# optical_meter_reader.net
KiCad netlist of a schematic drawn in EAGLE
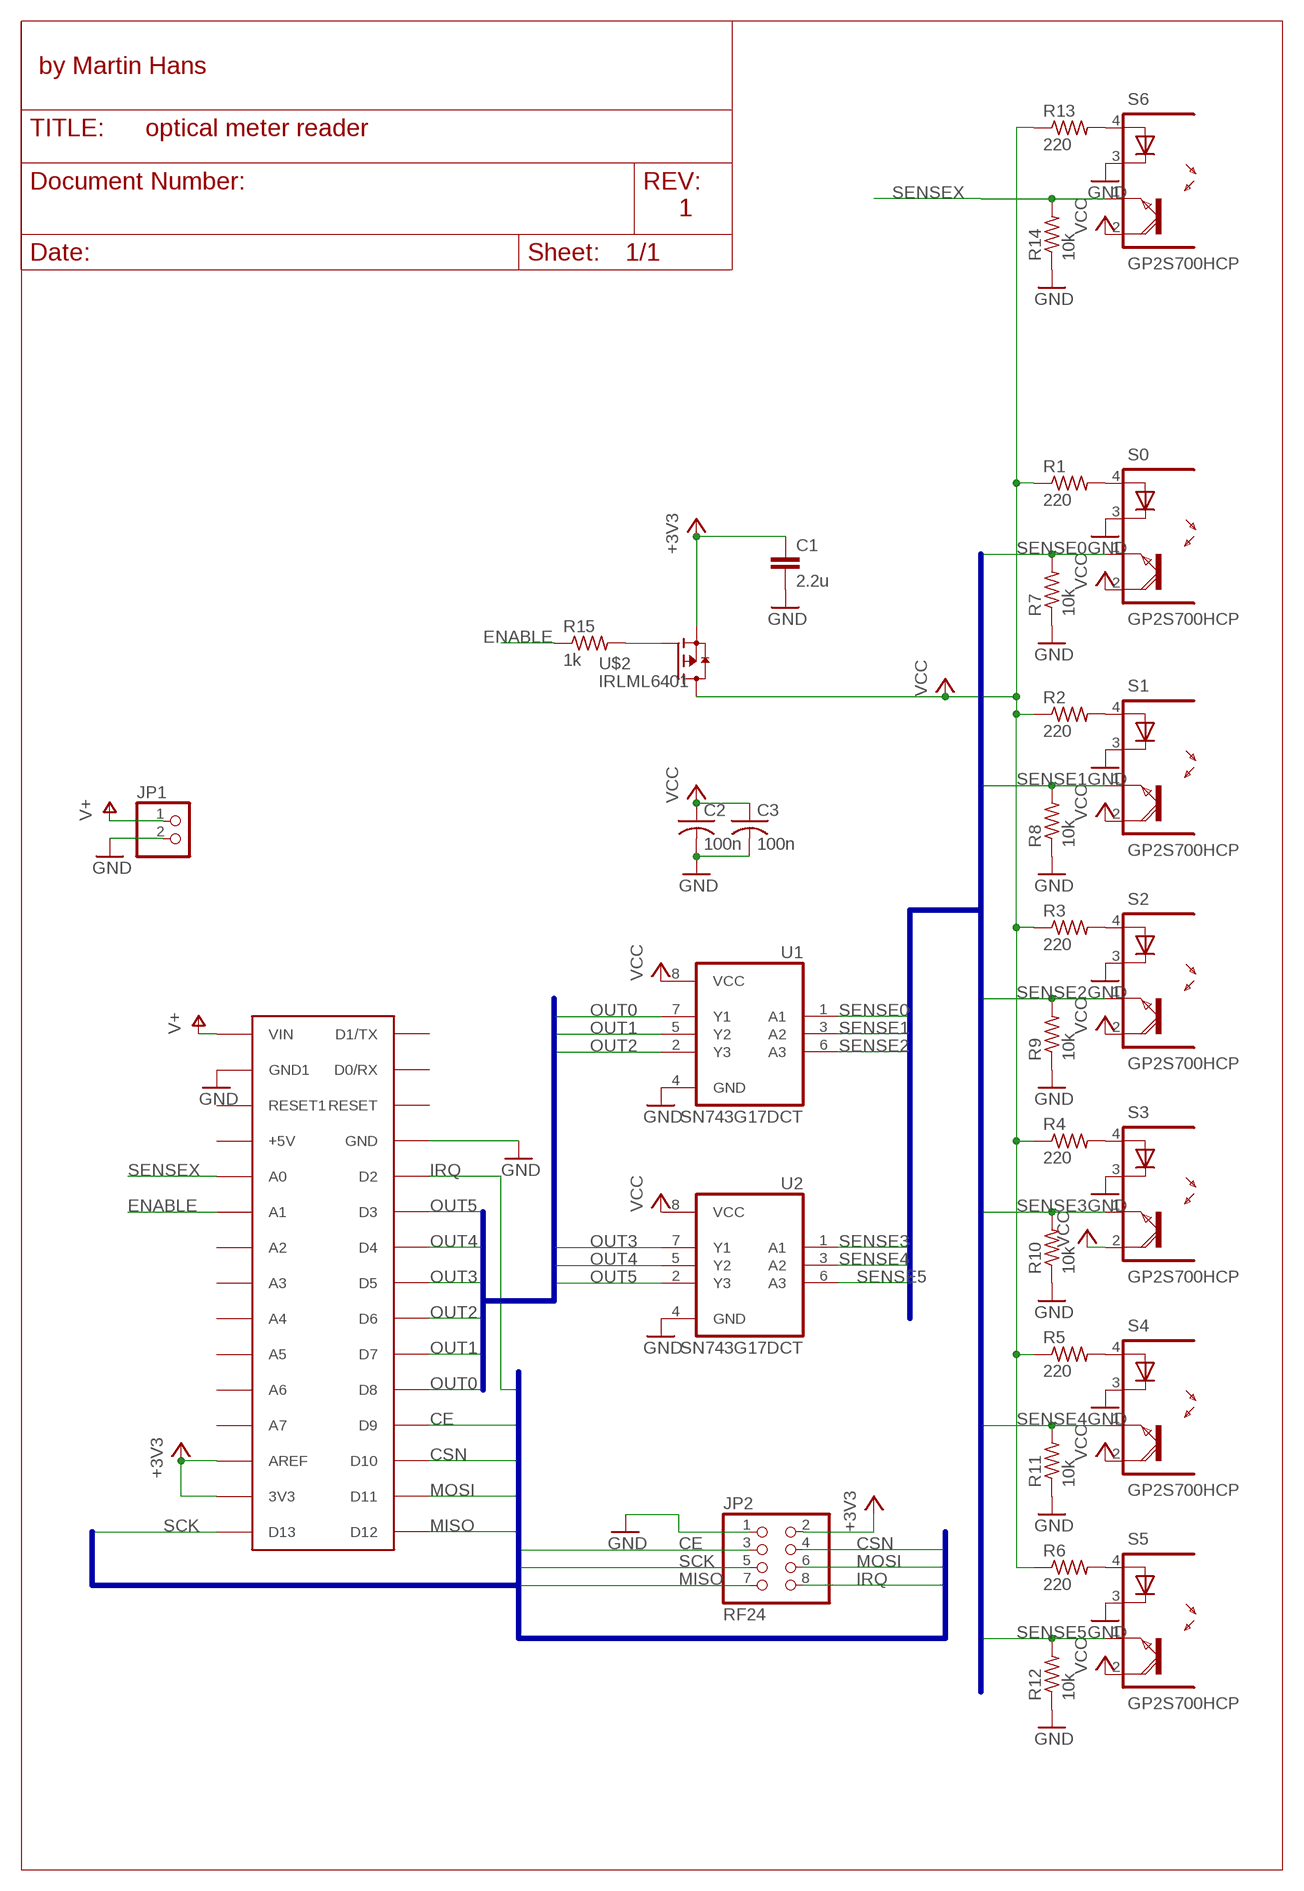
[diagram p0: schematic, sheet 1]

(export (version "E")
  (design (tool "Eeschema 10.0.6"))
  (components
    (comp (ref "C1")
      (value "2.2u")
      (footprint "eagle-import:C0603")
      (libsource (lib "eagle-import") (part "C-EUC0603"))
    )
    (comp (ref "C2")
      (value "100n")
      (footprint "eagle-import:C0603")
      (libsource (lib "eagle-import") (part "C-USC0603"))
    )
    (comp (ref "C3")
      (value "100n")
      (footprint "eagle-import:C0603")
      (libsource (lib "eagle-import") (part "C-USC0603"))
    )
    (comp (ref "JP1")
      (value "PINHD-1X2")
      (footprint "eagle-import:1X02")
      (libsource (lib "eagle-import") (part "PINHD-1X2"))
    )
    (comp (ref "JP2")
      (value "RF24")
      (footprint "eagle-import:2X04")
      (libsource (lib "eagle-import") (part "PINHD-2X4"))
    )
    (comp (ref "R1")
      (value "220")
      (footprint "eagle-import:R0603")
      (libsource (lib "eagle-import") (part "R-US_R0603"))
    )
    (comp (ref "R2")
      (value "220")
      (footprint "eagle-import:R0603")
      (libsource (lib "eagle-import") (part "R-US_R0603"))
    )
    (comp (ref "R3")
      (value "220")
      (footprint "eagle-import:R0603")
      (libsource (lib "eagle-import") (part "R-US_R0603"))
    )
    (comp (ref "R4")
      (value "220")
      (footprint "eagle-import:R0603")
      (libsource (lib "eagle-import") (part "R-US_R0603"))
    )
    (comp (ref "R5")
      (value "220")
      (footprint "eagle-import:R0603")
      (libsource (lib "eagle-import") (part "R-US_R0603"))
    )
    (comp (ref "R6")
      (value "220")
      (footprint "eagle-import:R0603")
      (libsource (lib "eagle-import") (part "R-US_R0603"))
    )
    (comp (ref "R7")
      (value "10k")
      (footprint "eagle-import:R0603")
      (libsource (lib "eagle-import") (part "R-US_R0603"))
    )
    (comp (ref "R8")
      (value "10k")
      (footprint "eagle-import:R0603")
      (libsource (lib "eagle-import") (part "R-US_R0603"))
    )
    (comp (ref "R9")
      (value "10k")
      (footprint "eagle-import:R0603")
      (libsource (lib "eagle-import") (part "R-US_R0603"))
    )
    (comp (ref "R10")
      (value "10k")
      (footprint "eagle-import:R0603")
      (libsource (lib "eagle-import") (part "R-US_R0603"))
    )
    (comp (ref "R11")
      (value "10k")
      (footprint "eagle-import:R0603")
      (libsource (lib "eagle-import") (part "R-US_R0603"))
    )
    (comp (ref "R12")
      (value "10k")
      (footprint "eagle-import:R0603")
      (libsource (lib "eagle-import") (part "R-US_R0603"))
    )
    (comp (ref "R13")
      (value "220")
      (footprint "eagle-import:R0603")
      (libsource (lib "eagle-import") (part "R-US_R0603"))
    )
    (comp (ref "R14")
      (value "10k")
      (footprint "eagle-import:R0603")
      (libsource (lib "eagle-import") (part "R-US_R0603"))
    )
    (comp (ref "R15")
      (value "1k")
      (footprint "eagle-import:R0603")
      (libsource (lib "eagle-import") (part "R-US_R0603"))
    )
    (comp (ref "S0")
      (value "GP2S700HCP")
      (footprint "eagle-import:SMD")
      (libsource (lib "eagle-import") (part "GP2S700HCP"))
    )
    (comp (ref "S1")
      (value "GP2S700HCP")
      (footprint "eagle-import:SMD")
      (libsource (lib "eagle-import") (part "GP2S700HCP"))
    )
    (comp (ref "S2")
      (value "GP2S700HCP")
      (footprint "eagle-import:SMD")
      (libsource (lib "eagle-import") (part "GP2S700HCP"))
    )
    (comp (ref "S3")
      (value "GP2S700HCP")
      (footprint "eagle-import:SMD")
      (libsource (lib "eagle-import") (part "GP2S700HCP"))
    )
    (comp (ref "S4")
      (value "GP2S700HCP")
      (footprint "eagle-import:SMD")
      (libsource (lib "eagle-import") (part "GP2S700HCP"))
    )
    (comp (ref "S5")
      (value "GP2S700HCP")
      (footprint "eagle-import:SMD")
      (libsource (lib "eagle-import") (part "GP2S700HCP"))
    )
    (comp (ref "S6")
      (value "GP2S700HCP")
      (footprint "eagle-import:SMD")
      (libsource (lib "eagle-import") (part "GP2S700HCP"))
    )
    (comp (ref "U$1")
      (value "ARDUINONANO")
      (footprint "eagle-import:PDIP-32")
      (libsource (lib "eagle-import") (part "ARDUINONANO"))
    )
    (comp (ref "U$2")
      (value "IRLML6401")
      (footprint "eagle-import:SOT23")
      (libsource (lib "eagle-import") (part "IRLML6401"))
    )
    (comp (ref "U1")
      (value "SN743G17DCT")
      (footprint "eagle-import:SSOP08")
      (libsource (lib "eagle-import") (part "SN743G17DCT"))
    )
    (comp (ref "U2")
      (value "SN743G17DCT")
      (footprint "eagle-import:SSOP08")
      (libsource (lib "eagle-import") (part "SN743G17DCT"))
    )
  )
  (nets
    (net (code "1") (name "+3V3") (class "Default")
      (node (ref "C1") (pin "1") (pinfunction "1_1") (pintype "passive"))
      (node (ref "JP2") (pin "2") (pinfunction "2_2") (pintype "passive"))
      (node (ref "U$1") (pin "3V3") (pinfunction "3V3_3V3") (pintype "bidirectional"))
      (node (ref "U$1") (pin "AREF") (pinfunction "AREF_AREF") (pintype "bidirectional"))
      (node (ref "U$2") (pin "2") (pinfunction "S_2") (pintype "passive"))
    )
    (net (code "2") (name "/CE") (class "Default")
      (node (ref "JP2") (pin "3") (pinfunction "3_3") (pintype "passive"))
      (node (ref "U$1") (pin "D9") (pinfunction "D9_D9") (pintype "bidirectional"))
    )
    (net (code "3") (name "/CSN") (class "Default")
      (node (ref "JP2") (pin "4") (pinfunction "4_4") (pintype "passive"))
      (node (ref "U$1") (pin "D10") (pinfunction "D10_D10") (pintype "bidirectional"))
    )
    (net (code "4") (name "/ENABLE") (class "Default")
      (node (ref "R15") (pin "1") (pinfunction "1_1") (pintype "passive"))
      (node (ref "U$1") (pin "A1") (pinfunction "A1_A1") (pintype "bidirectional"))
    )
    (net (code "5") (name "/IRQ") (class "Default")
      (node (ref "JP2") (pin "8") (pinfunction "8_8") (pintype "passive"))
      (node (ref "U$1") (pin "D2") (pinfunction "D2_D2") (pintype "bidirectional"))
    )
    (net (code "6") (name "/MISO") (class "Default")
      (node (ref "JP2") (pin "7") (pinfunction "7_7") (pintype "passive"))
      (node (ref "U$1") (pin "D12") (pinfunction "D12_D12") (pintype "bidirectional"))
    )
    (net (code "7") (name "/MOSI") (class "Default")
      (node (ref "JP2") (pin "6") (pinfunction "6_6") (pintype "passive"))
      (node (ref "U$1") (pin "D11") (pinfunction "D11_D11") (pintype "bidirectional"))
    )
    (net (code "8") (name "/OUT0") (class "Default")
      (node (ref "U$1") (pin "D8") (pinfunction "D8_D8") (pintype "bidirectional"))
      (node (ref "U1") (pin "7") (pinfunction "Y1_7") (pintype "tri_state"))
    )
    (net (code "9") (name "/OUT1") (class "Default")
      (node (ref "U$1") (pin "D7") (pinfunction "D7_D7") (pintype "bidirectional"))
      (node (ref "U1") (pin "5") (pinfunction "Y2_5") (pintype "tri_state"))
    )
    (net (code "10") (name "/OUT2") (class "Default")
      (node (ref "U$1") (pin "D6") (pinfunction "D6_D6") (pintype "bidirectional"))
      (node (ref "U1") (pin "2") (pinfunction "Y3_2") (pintype "tri_state"))
    )
    (net (code "11") (name "/OUT3") (class "Default")
      (node (ref "U$1") (pin "D5") (pinfunction "D5_D5") (pintype "bidirectional"))
      (node (ref "U2") (pin "7") (pinfunction "Y1_7") (pintype "tri_state"))
    )
    (net (code "12") (name "/OUT4") (class "Default")
      (node (ref "U$1") (pin "D4") (pinfunction "D4_D4") (pintype "bidirectional"))
      (node (ref "U2") (pin "5") (pinfunction "Y2_5") (pintype "tri_state"))
    )
    (net (code "13") (name "/OUT5") (class "Default")
      (node (ref "U$1") (pin "D3") (pinfunction "D3_D3") (pintype "bidirectional"))
      (node (ref "U2") (pin "2") (pinfunction "Y3_2") (pintype "tri_state"))
    )
    (net (code "14") (name "/SCK") (class "Default")
      (node (ref "JP2") (pin "5") (pinfunction "5_5") (pintype "passive"))
      (node (ref "U$1") (pin "D13") (pinfunction "D13_D13") (pintype "bidirectional"))
    )
    (net (code "15") (name "/SENSE0") (class "Default")
      (node (ref "R7") (pin "2") (pinfunction "2_2") (pintype "passive"))
      (node (ref "S0") (pin "1") (pinfunction "EMI_1") (pintype "passive"))
      (node (ref "U1") (pin "1") (pinfunction "A1_1") (pintype "tri_state"))
    )
    (net (code "16") (name "/SENSE1") (class "Default")
      (node (ref "R8") (pin "2") (pinfunction "2_2") (pintype "passive"))
      (node (ref "S1") (pin "1") (pinfunction "EMI_1") (pintype "passive"))
      (node (ref "U1") (pin "3") (pinfunction "A2_3") (pintype "tri_state"))
    )
    (net (code "17") (name "/SENSE2") (class "Default")
      (node (ref "R9") (pin "2") (pinfunction "2_2") (pintype "passive"))
      (node (ref "S2") (pin "1") (pinfunction "EMI_1") (pintype "passive"))
      (node (ref "U1") (pin "6") (pinfunction "A3_6") (pintype "tri_state"))
    )
    (net (code "18") (name "/SENSE3") (class "Default")
      (node (ref "R10") (pin "2") (pinfunction "2_2") (pintype "passive"))
      (node (ref "S3") (pin "1") (pinfunction "EMI_1") (pintype "passive"))
      (node (ref "U2") (pin "1") (pinfunction "A1_1") (pintype "tri_state"))
    )
    (net (code "19") (name "/SENSE4") (class "Default")
      (node (ref "R11") (pin "2") (pinfunction "2_2") (pintype "passive"))
      (node (ref "S4") (pin "1") (pinfunction "EMI_1") (pintype "passive"))
      (node (ref "U2") (pin "3") (pinfunction "A2_3") (pintype "tri_state"))
    )
    (net (code "20") (name "/SENSE5") (class "Default")
      (node (ref "R12") (pin "2") (pinfunction "2_2") (pintype "passive"))
      (node (ref "S5") (pin "1") (pinfunction "EMI_1") (pintype "passive"))
      (node (ref "U2") (pin "6") (pinfunction "A3_6") (pintype "tri_state"))
    )
    (net (code "21") (name "/SENSEX") (class "Default")
      (node (ref "R14") (pin "2") (pinfunction "2_2") (pintype "passive"))
      (node (ref "S6") (pin "1") (pinfunction "EMI_1") (pintype "passive"))
      (node (ref "U$1") (pin "A0") (pinfunction "A0_A0") (pintype "bidirectional"))
    )
    (net (code "22") (name "GND") (class "Default")
      (node (ref "C1") (pin "2") (pinfunction "2_2") (pintype "passive"))
      (node (ref "C2") (pin "2") (pinfunction "2_2") (pintype "passive"))
      (node (ref "C3") (pin "2") (pinfunction "2_2") (pintype "passive"))
      (node (ref "JP1") (pin "2") (pinfunction "2_2") (pintype "passive"))
      (node (ref "JP2") (pin "1") (pinfunction "1_1") (pintype "passive"))
      (node (ref "R10") (pin "1") (pinfunction "1_1") (pintype "passive"))
      (node (ref "R11") (pin "1") (pinfunction "1_1") (pintype "passive"))
      (node (ref "R12") (pin "1") (pinfunction "1_1") (pintype "passive"))
      (node (ref "R14") (pin "1") (pinfunction "1_1") (pintype "passive"))
      (node (ref "R7") (pin "1") (pinfunction "1_1") (pintype "passive"))
      (node (ref "R8") (pin "1") (pinfunction "1_1") (pintype "passive"))
      (node (ref "R9") (pin "1") (pinfunction "1_1") (pintype "passive"))
      (node (ref "S0") (pin "3") (pinfunction "C_3") (pintype "passive"))
      (node (ref "S1") (pin "3") (pinfunction "C_3") (pintype "passive"))
      (node (ref "S2") (pin "3") (pinfunction "C_3") (pintype "passive"))
      (node (ref "S3") (pin "3") (pinfunction "C_3") (pintype "passive"))
      (node (ref "S4") (pin "3") (pinfunction "C_3") (pintype "passive"))
      (node (ref "S5") (pin "3") (pinfunction "C_3") (pintype "passive"))
      (node (ref "S6") (pin "3") (pinfunction "C_3") (pintype "passive"))
      (node (ref "U$1") (pin "GND") (pinfunction "GND_GND") (pintype "bidirectional"))
      (node (ref "U$1") (pin "GND1") (pinfunction "GND1_GND1") (pintype "bidirectional"))
      (node (ref "U1") (pin "4") (pinfunction "GND_4") (pintype "power_in"))
      (node (ref "U2") (pin "4") (pinfunction "GND_4") (pintype "power_in"))
    )
    (net (code "23") (name "Net-(S0-A)") (class "Default")
      (node (ref "R1") (pin "2") (pinfunction "2_2") (pintype "passive"))
      (node (ref "S0") (pin "4") (pinfunction "A_4") (pintype "passive"))
    )
    (net (code "24") (name "Net-(S1-A)") (class "Default")
      (node (ref "R2") (pin "2") (pinfunction "2_2") (pintype "passive"))
      (node (ref "S1") (pin "4") (pinfunction "A_4") (pintype "passive"))
    )
    (net (code "25") (name "Net-(S2-A)") (class "Default")
      (node (ref "R3") (pin "2") (pinfunction "2_2") (pintype "passive"))
      (node (ref "S2") (pin "4") (pinfunction "A_4") (pintype "passive"))
    )
    (net (code "26") (name "Net-(S3-A)") (class "Default")
      (node (ref "R4") (pin "2") (pinfunction "2_2") (pintype "passive"))
      (node (ref "S3") (pin "4") (pinfunction "A_4") (pintype "passive"))
    )
    (net (code "27") (name "Net-(S4-A)") (class "Default")
      (node (ref "R5") (pin "2") (pinfunction "2_2") (pintype "passive"))
      (node (ref "S4") (pin "4") (pinfunction "A_4") (pintype "passive"))
    )
    (net (code "28") (name "Net-(S5-A)") (class "Default")
      (node (ref "R6") (pin "2") (pinfunction "2_2") (pintype "passive"))
      (node (ref "S5") (pin "4") (pinfunction "A_4") (pintype "passive"))
    )
    (net (code "29") (name "Net-(S6-A)") (class "Default")
      (node (ref "R13") (pin "2") (pinfunction "2_2") (pintype "passive"))
      (node (ref "S6") (pin "4") (pinfunction "A_4") (pintype "passive"))
    )
    (net (code "30") (name "Net-(U$2-G)") (class "Default")
      (node (ref "R15") (pin "2") (pinfunction "2_2") (pintype "passive"))
      (node (ref "U$2") (pin "1") (pinfunction "G_1") (pintype "passive"))
    )
    (net (code "31") (name "V+") (class "Default")
      (node (ref "JP1") (pin "1") (pinfunction "1_1") (pintype "passive"))
      (node (ref "U$1") (pin "VIN") (pinfunction "VIN_VIN") (pintype "bidirectional"))
    )
    (net (code "32") (name "VCC") (class "Default")
      (node (ref "C2") (pin "1") (pinfunction "1_1") (pintype "passive"))
      (node (ref "C3") (pin "1") (pinfunction "1_1") (pintype "passive"))
      (node (ref "R1") (pin "1") (pinfunction "1_1") (pintype "passive"))
      (node (ref "R13") (pin "1") (pinfunction "1_1") (pintype "passive"))
      (node (ref "R2") (pin "1") (pinfunction "1_1") (pintype "passive"))
      (node (ref "R3") (pin "1") (pinfunction "1_1") (pintype "passive"))
      (node (ref "R4") (pin "1") (pinfunction "1_1") (pintype "passive"))
      (node (ref "R5") (pin "1") (pinfunction "1_1") (pintype "passive"))
      (node (ref "R6") (pin "1") (pinfunction "1_1") (pintype "passive"))
      (node (ref "S0") (pin "2") (pinfunction "COL_2") (pintype "passive"))
      (node (ref "S1") (pin "2") (pinfunction "COL_2") (pintype "passive"))
      (node (ref "S2") (pin "2") (pinfunction "COL_2") (pintype "passive"))
      (node (ref "S3") (pin "2") (pinfunction "COL_2") (pintype "passive"))
      (node (ref "S4") (pin "2") (pinfunction "COL_2") (pintype "passive"))
      (node (ref "S5") (pin "2") (pinfunction "COL_2") (pintype "passive"))
      (node (ref "S6") (pin "2") (pinfunction "COL_2") (pintype "passive"))
      (node (ref "U$2") (pin "3") (pinfunction "D_3") (pintype "passive"))
      (node (ref "U1") (pin "8") (pinfunction "VCC_8") (pintype "power_in"))
      (node (ref "U2") (pin "8") (pinfunction "VCC_8") (pintype "power_in"))
    )
    (net (code "33") (name "unconnected-(U$1-Pad+5V)") (class "Default")
      (node (ref "U$1") (pin "+5V") (pinfunction "+5V_+5V") (pintype "bidirectional"))
    )
    (net (code "34") (name "unconnected-(U$1-PadA2)") (class "Default")
      (node (ref "U$1") (pin "A2") (pinfunction "A2_A2") (pintype "bidirectional"))
    )
    (net (code "35") (name "unconnected-(U$1-PadA3)") (class "Default")
      (node (ref "U$1") (pin "A3") (pinfunction "A3_A3") (pintype "bidirectional"))
    )
    (net (code "36") (name "unconnected-(U$1-PadA4)") (class "Default")
      (node (ref "U$1") (pin "A4") (pinfunction "A4_A4") (pintype "bidirectional"))
    )
    (net (code "37") (name "unconnected-(U$1-PadA5)") (class "Default")
      (node (ref "U$1") (pin "A5") (pinfunction "A5_A5") (pintype "bidirectional"))
    )
    (net (code "38") (name "unconnected-(U$1-PadA6)") (class "Default")
      (node (ref "U$1") (pin "A6") (pinfunction "A6_A6") (pintype "bidirectional"))
    )
    (net (code "39") (name "unconnected-(U$1-PadA7)") (class "Default")
      (node (ref "U$1") (pin "A7") (pinfunction "A7_A7") (pintype "bidirectional"))
    )
    (net (code "40") (name "unconnected-(U$1-PadD0{slash}RX)") (class "Default")
      (node (ref "U$1") (pin "D0/RX") (pinfunction "D0/RX_D0/RX") (pintype "bidirectional"))
    )
    (net (code "41") (name "unconnected-(U$1-PadD1{slash}TX)") (class "Default")
      (node (ref "U$1") (pin "D1/TX") (pinfunction "D1/TX_D1/TX") (pintype "bidirectional"))
    )
    (net (code "42") (name "unconnected-(U$1-PadRESET)") (class "Default")
      (node (ref "U$1") (pin "RESET") (pinfunction "RESET_RESET") (pintype "bidirectional"))
    )
    (net (code "43") (name "unconnected-(U$1-PadRESET1)") (class "Default")
      (node (ref "U$1") (pin "RESET1") (pinfunction "RESET1_RESET1") (pintype "bidirectional"))
    )
  )
)
